# 02_-_MCU.net
KiCad netlist of a schematic drawn in Altium Designer
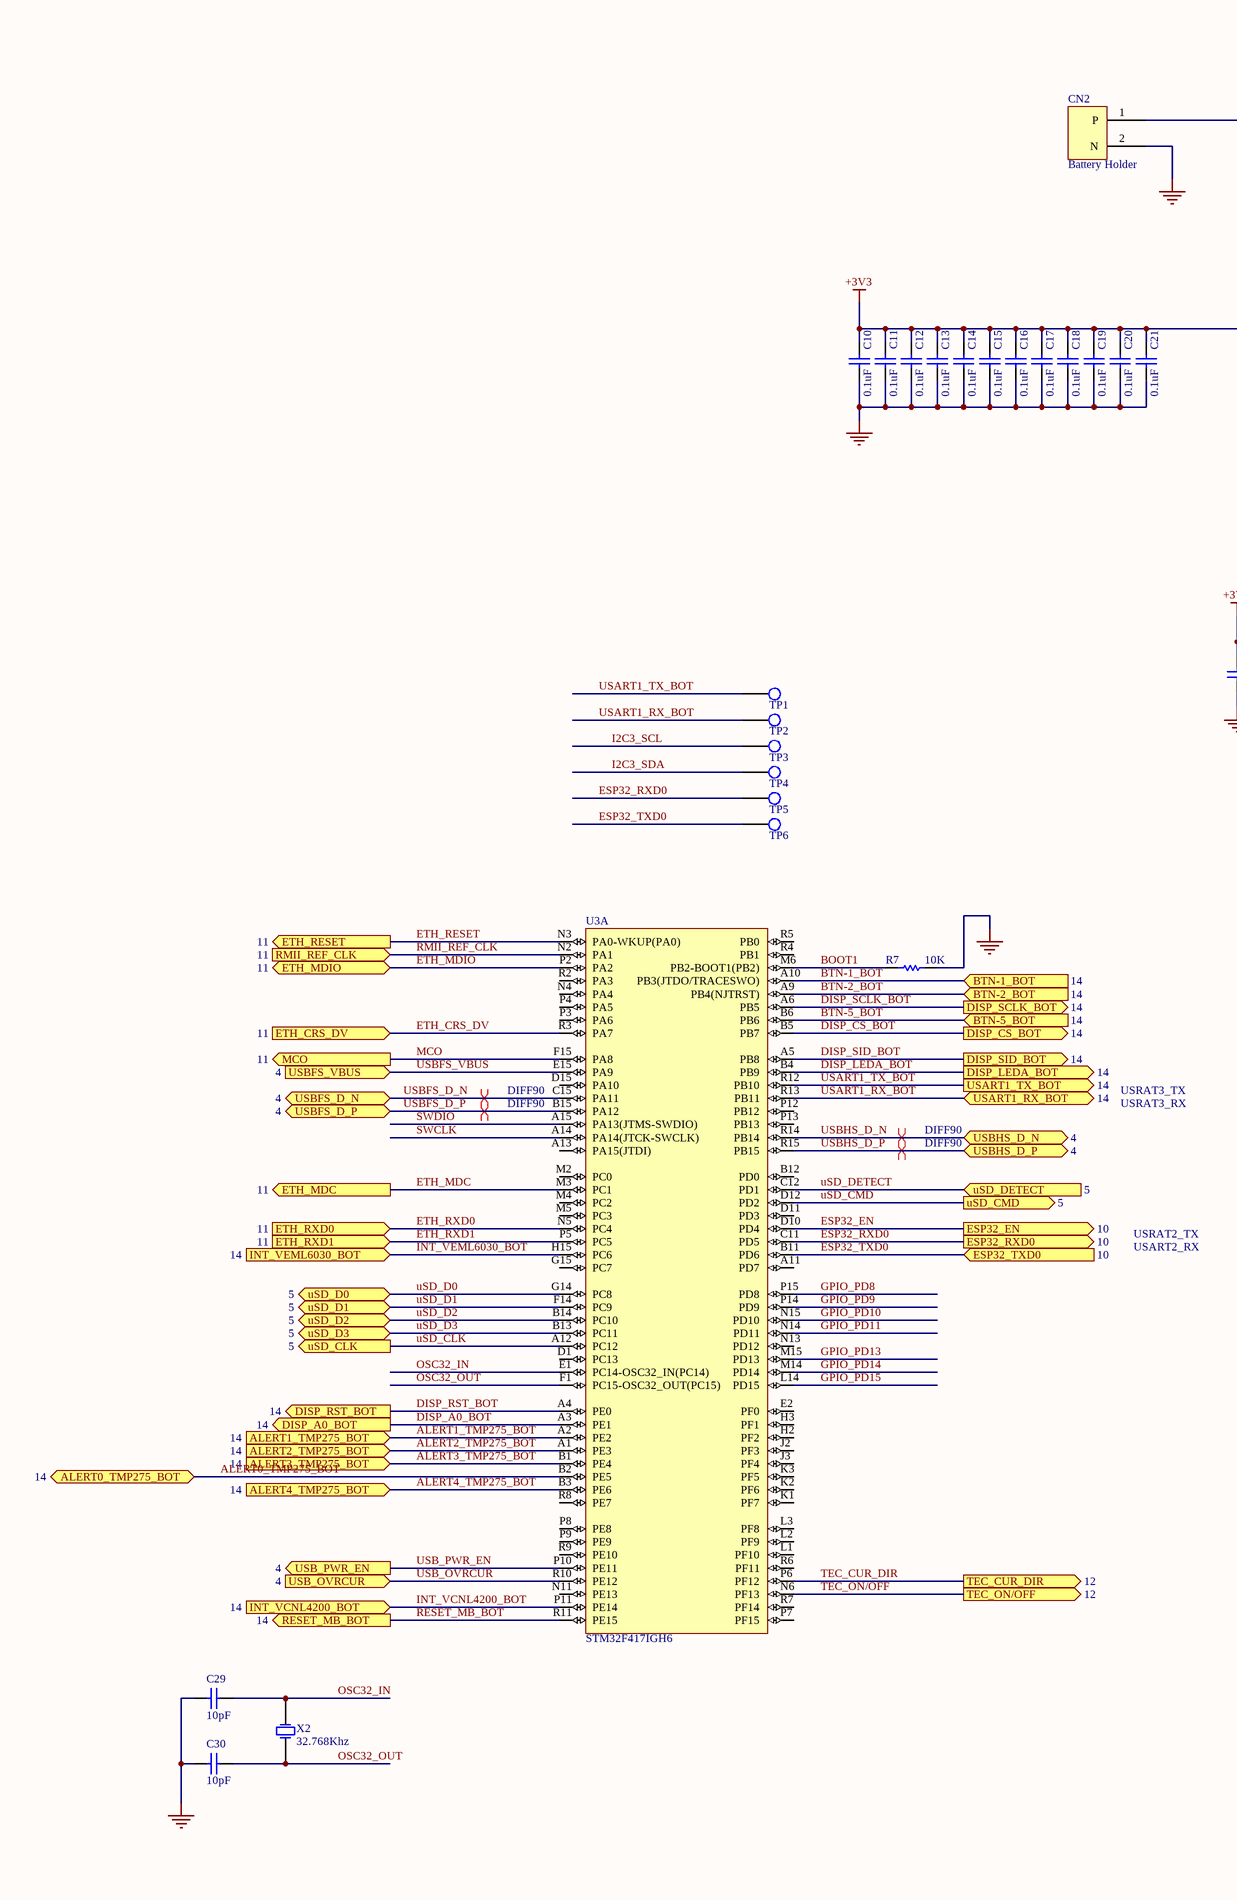
[diagram p0: [02] - MCU.SchDoc, left]
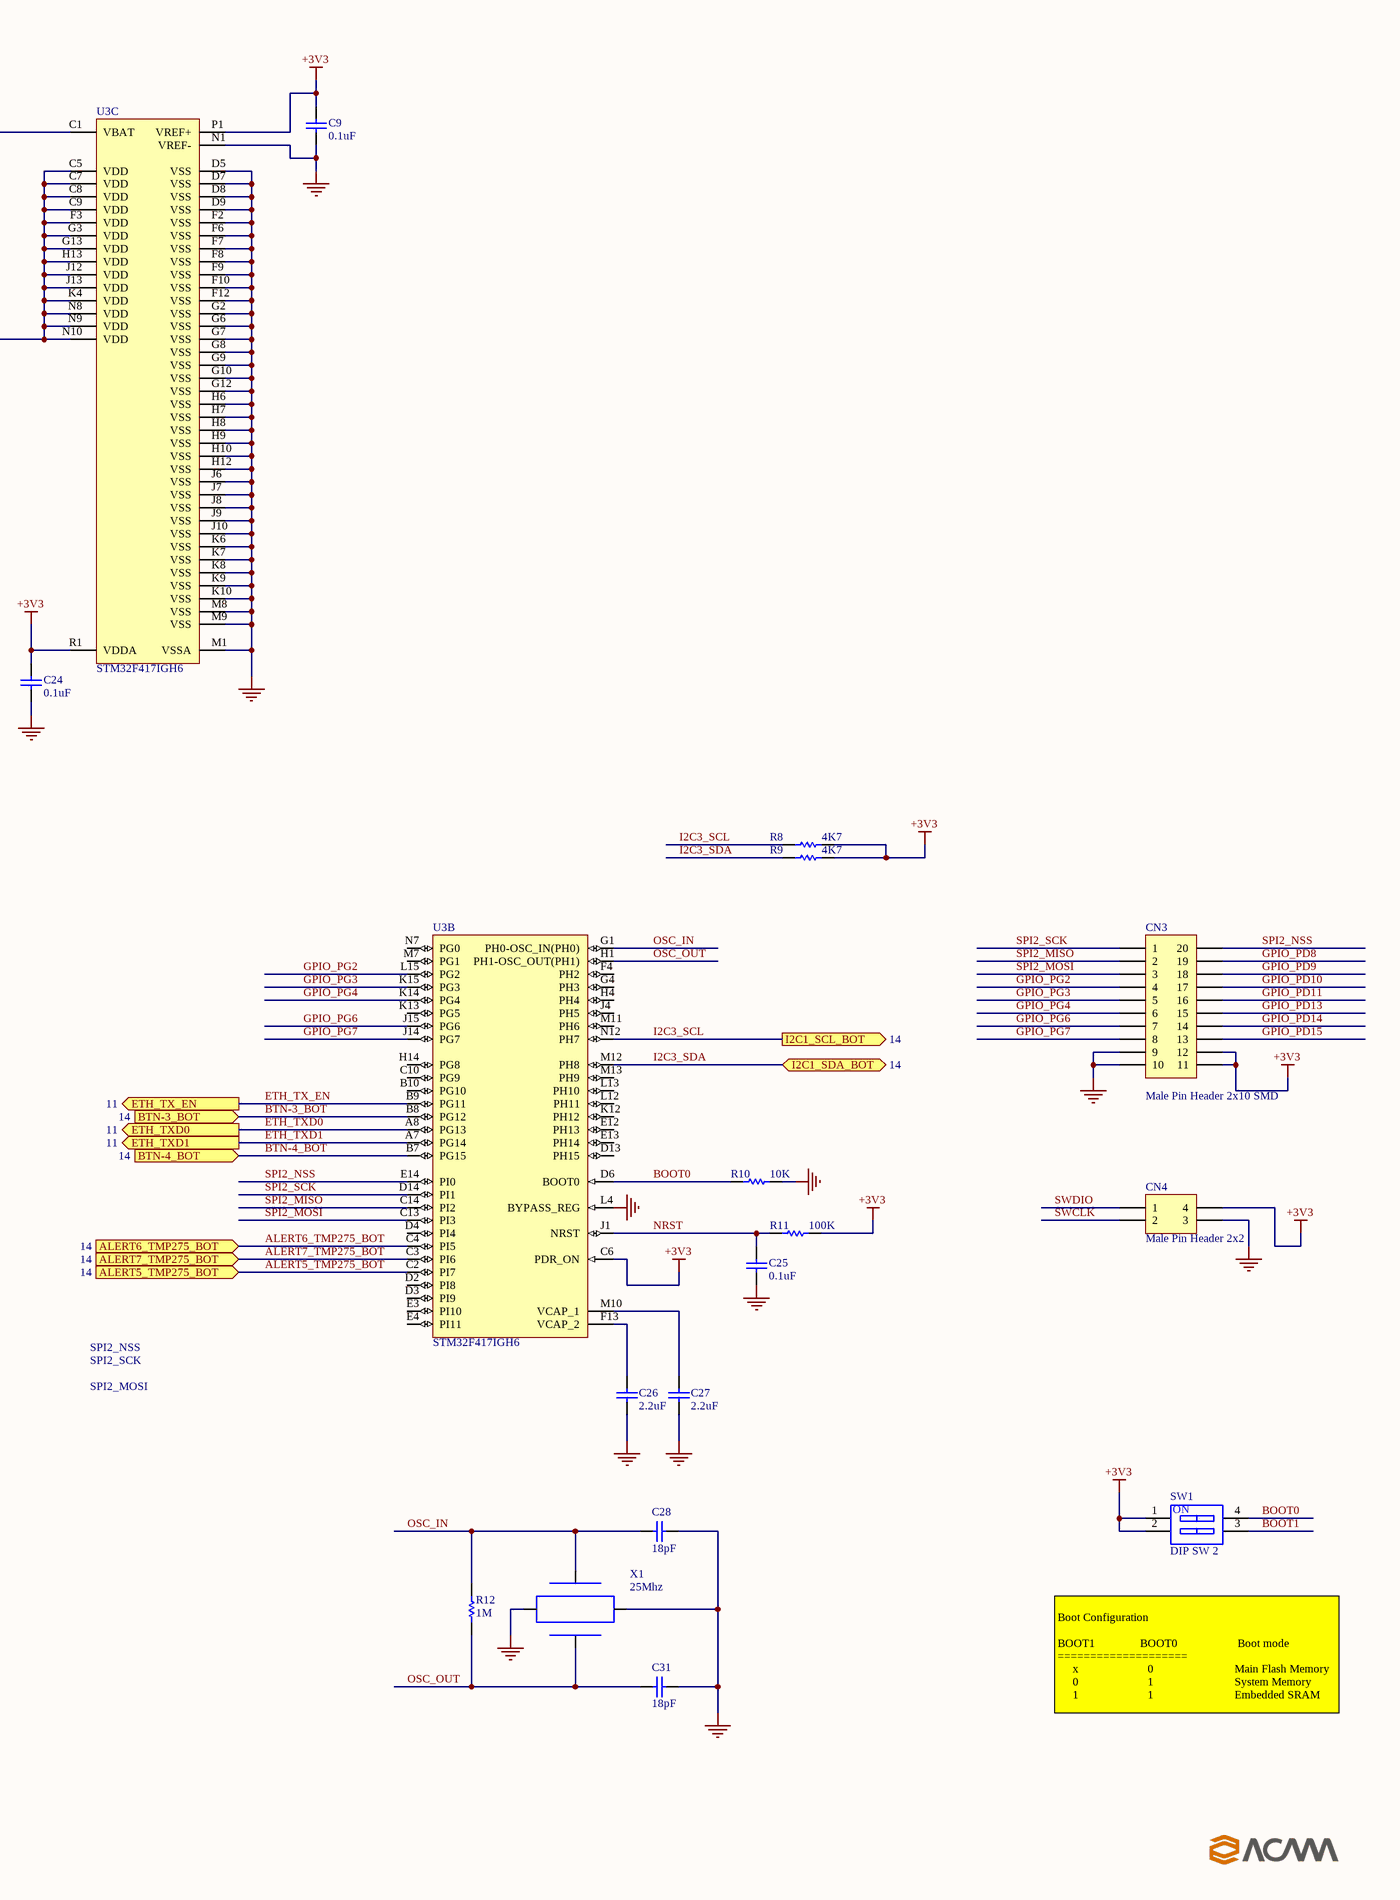
[diagram p1: [02] - MCU.SchDoc, right]

(export (version "E")
  (design (tool "Eeschema 10.0.6"))
  (components
    (comp (ref "C9")
      (value "0.1uF")
      (footprint "0402_C_AUTO")
      (description "Non-Pol SMD Capacitor")
      (libsource (lib "Farzan Custom Library") (part "Cap SMD"))
    )
    (comp (ref "C10")
      (value "0.1uF")
      (footprint "0402_C_AUTO")
      (description "Non-Pol SMD Capacitor")
      (libsource (lib "Farzan Custom Library") (part "Cap SMD"))
    )
    (comp (ref "C11")
      (value "0.1uF")
      (footprint "0402_C_AUTO")
      (description "Non-Pol SMD Capacitor")
      (libsource (lib "Farzan Custom Library") (part "Cap SMD"))
    )
    (comp (ref "C12")
      (value "0.1uF")
      (footprint "0402_C_AUTO")
      (description "Non-Pol SMD Capacitor")
      (libsource (lib "Farzan Custom Library") (part "Cap SMD"))
    )
    (comp (ref "C13")
      (value "0.1uF")
      (footprint "0402_C_AUTO")
      (description "Non-Pol SMD Capacitor")
      (libsource (lib "Farzan Custom Library") (part "Cap SMD"))
    )
    (comp (ref "C14")
      (value "0.1uF")
      (footprint "0402_C_AUTO")
      (description "Non-Pol SMD Capacitor")
      (libsource (lib "Farzan Custom Library") (part "Cap SMD"))
    )
    (comp (ref "C15")
      (value "0.1uF")
      (footprint "0402_C_AUTO")
      (description "Non-Pol SMD Capacitor")
      (libsource (lib "Farzan Custom Library") (part "Cap SMD"))
    )
    (comp (ref "C16")
      (value "0.1uF")
      (footprint "0402_C_AUTO")
      (description "Non-Pol SMD Capacitor")
      (libsource (lib "Farzan Custom Library") (part "Cap SMD"))
    )
    (comp (ref "C17")
      (value "0.1uF")
      (footprint "0402_C_AUTO")
      (description "Non-Pol SMD Capacitor")
      (libsource (lib "Farzan Custom Library") (part "Cap SMD"))
    )
    (comp (ref "C18")
      (value "0.1uF")
      (footprint "0402_C_AUTO")
      (description "Non-Pol SMD Capacitor")
      (libsource (lib "Farzan Custom Library") (part "Cap SMD"))
    )
    (comp (ref "C19")
      (value "0.1uF")
      (footprint "0402_C_AUTO")
      (description "Non-Pol SMD Capacitor")
      (libsource (lib "Farzan Custom Library") (part "Cap SMD"))
    )
    (comp (ref "C20")
      (value "0.1uF")
      (footprint "0402_C_AUTO")
      (description "Non-Pol SMD Capacitor")
      (libsource (lib "Farzan Custom Library") (part "Cap SMD"))
    )
    (comp (ref "C21")
      (value "0.1uF")
      (footprint "0402_C_AUTO")
      (description "Non-Pol SMD Capacitor")
      (libsource (lib "Farzan Custom Library") (part "Cap SMD"))
    )
    (comp (ref "C24")
      (value "0.1uF")
      (footprint "0402_C_AUTO")
      (description "Non-Pol SMD Capacitor")
      (libsource (lib "Farzan Custom Library") (part "Cap SMD"))
    )
    (comp (ref "C25")
      (value "0.1uF")
      (footprint "0402_C_AUTO")
      (description "Non-Pol SMD Capacitor")
      (libsource (lib "Farzan Custom Library") (part "Cap SMD"))
    )
    (comp (ref "C26")
      (value "2.2uF")
      (footprint "0402_C_AUTO")
      (description "Non-Pol SMD Capacitor")
      (libsource (lib "Farzan Custom Library") (part "Cap SMD"))
    )
    (comp (ref "C27")
      (value "2.2uF")
      (footprint "0402_C_AUTO")
      (description "Non-Pol SMD Capacitor")
      (libsource (lib "Farzan Custom Library") (part "Cap SMD"))
    )
    (comp (ref "C28")
      (value "18pF")
      (footprint "0402_C_AUTO")
      (description "Non-Pol SMD Capacitor")
      (libsource (lib "Farzan Custom Library") (part "Cap SMD"))
    )
    (comp (ref "C29")
      (value "10pF")
      (footprint "0402_C_AUTO")
      (description "Non-Pol SMD Capacitor")
      (libsource (lib "Farzan Custom Library") (part "Cap SMD"))
    )
    (comp (ref "C30")
      (value "10pF")
      (footprint "0402_C_AUTO")
      (description "Non-Pol SMD Capacitor")
      (libsource (lib "Farzan Custom Library") (part "Cap SMD"))
    )
    (comp (ref "C31")
      (value "18pF")
      (footprint "0402_C_AUTO")
      (description "Non-Pol SMD Capacitor")
      (libsource (lib "Farzan Custom Library") (part "Cap SMD"))
    )
    (comp (ref "CN2")
      (value "Battery Holder")
      (footprint "CR2032_BATT_HOLDER")
      (description "CR2032 Battery Holder SMD")
      (libsource (lib "Farzan Custom Library") (part "Battery Holder"))
    )
    (comp (ref "CN3")
      (value "Male Pin Header 2x10 SMD")
      (footprint "HEADER_SMD_2x10")
      (description "SMD Male Pin Header 2.54mm Pitch, 2x10")
      (libsource (lib "Farzan Custom Library") (part "Pin header Male 2x10 smd"))
    )
    (comp (ref "CN4")
      (value "Male Pin Header 2x2")
      (footprint "Header_2x2_RIGHT")
      (description "Male Pin Header 2.54mm Pitch, 2x2")
      (libsource (lib "Farzan Custom Library") (part "Pin header Male 2x2"))
    )
    (comp (ref "R7")
      (value "10K")
      (footprint "0402_R_AUTO")
      (description "SMD Resistor")
      (fields (field (name "TOLERANCE") "5%"))
      (libsource (lib "Farzan Custom Library") (part "Res SMD"))
    )
    (comp (ref "R8")
      (value "4K7")
      (footprint "0402_R")
      (description "SMD Resistor")
      (fields (field (name "TOLERANCE") "5%"))
      (libsource (lib "Farzan Custom Library") (part "Res SMD"))
    )
    (comp (ref "R9")
      (value "4K7")
      (footprint "0402_R")
      (description "SMD Resistor")
      (fields (field (name "TOLERANCE") "5%"))
      (libsource (lib "Farzan Custom Library") (part "Res SMD"))
    )
    (comp (ref "R10")
      (value "10K")
      (footprint "0402_R_AUTO")
      (description "SMD Resistor")
      (fields (field (name "TOLERANCE") "5%"))
      (libsource (lib "Farzan Custom Library") (part "Res SMD"))
    )
    (comp (ref "R11")
      (value "100K")
      (footprint "0402_R_AUTO")
      (description "SMD Resistor")
      (fields (field (name "TOLERANCE") "5%"))
      (libsource (lib "Farzan Custom Library") (part "Res SMD"))
    )
    (comp (ref "R12")
      (value "1M")
      (footprint "0402_R")
      (description "SMD Resistor")
      (fields (field (name "TOLERANCE") "5%"))
      (libsource (lib "Farzan Custom Library") (part "Res SMD"))
    )
    (comp (ref "SW1")
      (value "DIP SW 2")
      (footprint "DIP-SW-2-Piano")
      (description "DIP Switch, 2 Position, SPST")
      (fields (field (name "MANUFACTURER PART NUM") "BPA02B"))
      (libsource (lib "Farzan Custom Library") (part "DIP SW-2"))
    )
    (comp (ref "TP1")
      (value "Test Point")
      (footprint "PIN_1.5mm")
      (description "Test Point Footprint")
      (libsource (lib "Farzan Custom Library") (part "Test Point"))
    )
    (comp (ref "TP2")
      (value "Test Point")
      (footprint "PIN_1.5mm")
      (description "Test Point Footprint")
      (libsource (lib "Farzan Custom Library") (part "Test Point"))
    )
    (comp (ref "TP3")
      (value "Test Point")
      (footprint "PIN_1.5mm")
      (description "Test Point Footprint")
      (libsource (lib "Farzan Custom Library") (part "Test Point"))
    )
    (comp (ref "TP4")
      (value "Test Point")
      (footprint "PIN_1.5mm")
      (description "Test Point Footprint")
      (libsource (lib "Farzan Custom Library") (part "Test Point"))
    )
    (comp (ref "TP5")
      (value "Test Point")
      (footprint "PIN_1mm")
      (description "Test Point Footprint")
      (libsource (lib "Farzan Custom Library") (part "Test Point"))
    )
    (comp (ref "TP6")
      (value "Test Point")
      (footprint "PIN_1mm")
      (description "Test Point Footprint")
      (libsource (lib "Farzan Custom Library") (part "Test Point"))
    )
    (comp (ref "U3")
      (value "STM32F417IGH6")
      (footprint "STM-UFBGA176+25")
      (fields (field (name "MANUFACTURER") "STMicroelectronics"))
      (libsource (lib "STMicroelectronics STM32 F4") (part "STM32F417IGH6"))
    )
    (comp (ref "X1")
      (value "25Mhz")
      (footprint "OSC_3.2x2.5")
      (description "4-pin SMD Crystal")
      (fields (field (name "MANUFACTURER PART NUM") "ECS-250-18-33-JTN-TR"))
      (libsource (lib "Farzan Custom Library") (part "XTAL 4pin"))
    )
    (comp (ref "X2")
      (value "32.768Khz")
      (footprint "XTAL_2.0x1.2")
      (description "2-pin SMD Crystal")
      (fields (field (name "MANUFACTURER PART NUM") "ECS-.327-12.5-12R-TR"))
      (libsource (lib "Farzan Custom Library") (part "XTAL"))
    )
  )
  (nets
    (net (code "1") (name "+3V3") (class "Default")
      (node (ref "C10") (pin "2") (pinfunction "2_2") (pintype "passive"))
      (node (ref "C11") (pin "2") (pinfunction "2_2") (pintype "passive"))
      (node (ref "C12") (pin "2") (pinfunction "2_2") (pintype "passive"))
      (node (ref "C13") (pin "2") (pinfunction "2_2") (pintype "passive"))
      (node (ref "C14") (pin "2") (pinfunction "2_2") (pintype "passive"))
      (node (ref "C15") (pin "2") (pinfunction "2_2") (pintype "passive"))
      (node (ref "C16") (pin "2") (pinfunction "2_2") (pintype "passive"))
      (node (ref "C17") (pin "2") (pinfunction "2_2") (pintype "passive"))
      (node (ref "C18") (pin "2") (pinfunction "2_2") (pintype "passive"))
      (node (ref "C19") (pin "2") (pinfunction "2_2") (pintype "passive"))
      (node (ref "C20") (pin "2") (pinfunction "2_2") (pintype "passive"))
      (node (ref "C21") (pin "2") (pinfunction "2_2") (pintype "passive"))
      (node (ref "C24") (pin "2") (pinfunction "2_2") (pintype "passive"))
      (node (ref "C9") (pin "2") (pinfunction "2_2") (pintype "passive"))
      (node (ref "CN3") (pin "11") (pinfunction "11_11") (pintype "passive"))
      (node (ref "CN3") (pin "12") (pinfunction "12_12") (pintype "passive"))
      (node (ref "CN4") (pin "4") (pinfunction "4_4") (pintype "passive"))
      (node (ref "R11") (pin "2") (pinfunction "2_2") (pintype "passive"))
      (node (ref "R8") (pin "1") (pinfunction "1_1") (pintype "passive"))
      (node (ref "R9") (pin "1") (pinfunction "1_1") (pintype "passive"))
      (node (ref "SW1") (pin "1") (pinfunction "A1_1") (pintype "passive"))
      (node (ref "SW1") (pin "2") (pinfunction "A2_2") (pintype "passive"))
      (node (ref "U3") (pin "C5") (pinfunction "VDD_C5") (pintype "power_in"))
      (node (ref "U3") (pin "C6") (pinfunction "PDR_ON_C6") (pintype "input"))
      (node (ref "U3") (pin "C7") (pinfunction "VDD_C7") (pintype "power_in"))
      (node (ref "U3") (pin "C8") (pinfunction "VDD_C8") (pintype "power_in"))
      (node (ref "U3") (pin "C9") (pinfunction "VDD_C9") (pintype "power_in"))
      (node (ref "U3") (pin "F3") (pinfunction "VDD_F3") (pintype "power_in"))
      (node (ref "U3") (pin "G13") (pinfunction "VDD_G13") (pintype "power_in"))
      (node (ref "U3") (pin "G3") (pinfunction "VDD_G3") (pintype "power_in"))
      (node (ref "U3") (pin "H13") (pinfunction "VDD_H13") (pintype "power_in"))
      (node (ref "U3") (pin "J12") (pinfunction "VDD_J12") (pintype "power_in"))
      (node (ref "U3") (pin "J13") (pinfunction "VDD_J13") (pintype "power_in"))
      (node (ref "U3") (pin "K4") (pinfunction "VDD_K4") (pintype "power_in"))
      (node (ref "U3") (pin "N10") (pinfunction "VDD_N10") (pintype "power_in"))
      (node (ref "U3") (pin "N8") (pinfunction "VDD_N8") (pintype "power_in"))
      (node (ref "U3") (pin "N9") (pinfunction "VDD_N9") (pintype "power_in"))
      (node (ref "U3") (pin "P1") (pinfunction "VREF+_P1") (pintype "power_in"))
      (node (ref "U3") (pin "R1") (pinfunction "VDDA_R1") (pintype "power_in"))
    )
    (net (code "2") (name "/ALERT0_TMP275_BOT") (class "Default")
      (node (ref "U3") (pin "B2") (pinfunction "PE5_B2") (pintype "bidirectional"))
    )
    (net (code "3") (name "/ALERT1_TMP275_BOT") (class "Default")
      (node (ref "U3") (pin "A2") (pinfunction "PE2_A2") (pintype "bidirectional"))
    )
    (net (code "4") (name "/ALERT2_TMP275_BOT") (class "Default")
      (node (ref "U3") (pin "A1") (pinfunction "PE3_A1") (pintype "bidirectional"))
    )
    (net (code "5") (name "/ALERT3_TMP275_BOT") (class "Default")
      (node (ref "U3") (pin "B1") (pinfunction "PE4_B1") (pintype "bidirectional"))
    )
    (net (code "6") (name "/ALERT4_TMP275_BOT") (class "Default")
      (node (ref "U3") (pin "B3") (pinfunction "PE6_B3") (pintype "bidirectional"))
    )
    (net (code "7") (name "/ALERT5_TMP275_BOT") (class "Default")
      (node (ref "U3") (pin "C2") (pinfunction "PI7_C2") (pintype "bidirectional"))
    )
    (net (code "8") (name "/ALERT6_TMP275_BOT") (class "Default")
      (node (ref "U3") (pin "C4") (pinfunction "PI5_C4") (pintype "bidirectional"))
    )
    (net (code "9") (name "/ALERT7_TMP275_BOT") (class "Default")
      (node (ref "U3") (pin "C3") (pinfunction "PI6_C3") (pintype "bidirectional"))
    )
    (net (code "10") (name "/BOOT0") (class "Default")
      (node (ref "R10") (pin "1") (pinfunction "1_1") (pintype "passive"))
      (node (ref "SW1") (pin "4") (pinfunction "A4_4") (pintype "passive"))
      (node (ref "U3") (pin "D6") (pinfunction "BOOT0_D6") (pintype "input"))
    )
    (net (code "11") (name "/BOOT1") (class "Default")
      (node (ref "R7") (pin "1") (pinfunction "1_1") (pintype "passive"))
      (node (ref "SW1") (pin "3") (pinfunction "A3_3") (pintype "passive"))
      (node (ref "U3") (pin "M6") (pinfunction "PB2-BOOT1(PB2)_M6") (pintype "bidirectional"))
    )
    (net (code "12") (name "/BTN-1_BOT") (class "Default")
      (node (ref "U3") (pin "A10") (pinfunction "PB3(JTDO/TRACESWO)_A10") (pintype "bidirectional"))
    )
    (net (code "13") (name "/BTN-2_BOT") (class "Default")
      (node (ref "U3") (pin "A9") (pinfunction "PB4(NJTRST)_A9") (pintype "bidirectional"))
    )
    (net (code "14") (name "/BTN-3_BOT") (class "Default")
      (node (ref "U3") (pin "B8") (pinfunction "PG12_B8") (pintype "bidirectional"))
    )
    (net (code "15") (name "/BTN-4_BOT") (class "Default")
      (node (ref "U3") (pin "B7") (pinfunction "PG15_B7") (pintype "bidirectional"))
    )
    (net (code "16") (name "/BTN-5_BOT") (class "Default")
      (node (ref "U3") (pin "B6") (pinfunction "PB6_B6") (pintype "bidirectional"))
    )
    (net (code "17") (name "/DISP_A0_BOT") (class "Default")
      (node (ref "U3") (pin "A3") (pinfunction "PE1_A3") (pintype "bidirectional"))
    )
    (net (code "18") (name "/DISP_CS_BOT") (class "Default")
      (node (ref "U3") (pin "B5") (pinfunction "PB7_B5") (pintype "bidirectional"))
    )
    (net (code "19") (name "/DISP_LEDA_BOT") (class "Default")
      (node (ref "U3") (pin "B4") (pinfunction "PB9_B4") (pintype "bidirectional"))
    )
    (net (code "20") (name "/DISP_RST_BOT") (class "Default")
      (node (ref "U3") (pin "A4") (pinfunction "PE0_A4") (pintype "bidirectional"))
    )
    (net (code "21") (name "/DISP_SCLK_BOT") (class "Default")
      (node (ref "U3") (pin "A6") (pinfunction "PB5_A6") (pintype "bidirectional"))
    )
    (net (code "22") (name "/DISP_SID_BOT") (class "Default")
      (node (ref "U3") (pin "A5") (pinfunction "PB8_A5") (pintype "bidirectional"))
    )
    (net (code "23") (name "/ESP32_EN") (class "Default")
      (node (ref "U3") (pin "D10") (pinfunction "PD4_D10") (pintype "bidirectional"))
    )
    (net (code "24") (name "/ESP32_RXD0") (class "Default")
      (node (ref "TP5") (pin "1") (pinfunction "1_1") (pintype "power_in"))
      (node (ref "U3") (pin "C11") (pinfunction "PD5_C11") (pintype "bidirectional"))
    )
    (net (code "25") (name "/ESP32_TXD0") (class "Default")
      (node (ref "TP6") (pin "1") (pinfunction "1_1") (pintype "power_in"))
      (node (ref "U3") (pin "B11") (pinfunction "PD6_B11") (pintype "bidirectional"))
    )
    (net (code "26") (name "/ETH_CRS_DV") (class "Default")
      (node (ref "U3") (pin "R3") (pinfunction "PA7_R3") (pintype "bidirectional"))
    )
    (net (code "27") (name "/ETH_MDC") (class "Default")
      (node (ref "U3") (pin "M3") (pinfunction "PC1_M3") (pintype "bidirectional"))
    )
    (net (code "28") (name "/ETH_MDIO") (class "Default")
      (node (ref "U3") (pin "P2") (pinfunction "PA2_P2") (pintype "bidirectional"))
    )
    (net (code "29") (name "/ETH_RESET") (class "Default")
      (node (ref "U3") (pin "N3") (pinfunction "PA0-WKUP(PA0)_N3") (pintype "bidirectional"))
    )
    (net (code "30") (name "/ETH_RXD0") (class "Default")
      (node (ref "U3") (pin "N5") (pinfunction "PC4_N5") (pintype "bidirectional"))
    )
    (net (code "31") (name "/ETH_RXD1") (class "Default")
      (node (ref "U3") (pin "P5") (pinfunction "PC5_P5") (pintype "bidirectional"))
    )
    (net (code "32") (name "/ETH_TXD0") (class "Default")
      (node (ref "U3") (pin "A8") (pinfunction "PG13_A8") (pintype "bidirectional"))
    )
    (net (code "33") (name "/ETH_TXD1") (class "Default")
      (node (ref "U3") (pin "A7") (pinfunction "PG14_A7") (pintype "bidirectional"))
    )
    (net (code "34") (name "/ETH_TX_EN") (class "Default")
      (node (ref "U3") (pin "B9") (pinfunction "PG11_B9") (pintype "bidirectional"))
    )
    (net (code "35") (name "/GPIO_PD8") (class "Default")
      (node (ref "CN3") (pin "19") (pinfunction "19_19") (pintype "passive"))
      (node (ref "U3") (pin "P15") (pinfunction "PD8_P15") (pintype "bidirectional"))
    )
    (net (code "36") (name "/GPIO_PD9") (class "Default")
      (node (ref "CN3") (pin "18") (pinfunction "18_18") (pintype "passive"))
      (node (ref "U3") (pin "P14") (pinfunction "PD9_P14") (pintype "bidirectional"))
    )
    (net (code "37") (name "/GPIO_PD10") (class "Default")
      (node (ref "CN3") (pin "17") (pinfunction "17_17") (pintype "passive"))
      (node (ref "U3") (pin "N15") (pinfunction "PD10_N15") (pintype "bidirectional"))
    )
    (net (code "38") (name "/GPIO_PD11") (class "Default")
      (node (ref "CN3") (pin "16") (pinfunction "16_16") (pintype "passive"))
      (node (ref "U3") (pin "N14") (pinfunction "PD11_N14") (pintype "bidirectional"))
    )
    (net (code "39") (name "/GPIO_PD13") (class "Default")
      (node (ref "CN3") (pin "15") (pinfunction "15_15") (pintype "passive"))
      (node (ref "U3") (pin "M15") (pinfunction "PD13_M15") (pintype "bidirectional"))
    )
    (net (code "40") (name "/GPIO_PD14") (class "Default")
      (node (ref "CN3") (pin "14") (pinfunction "14_14") (pintype "passive"))
      (node (ref "U3") (pin "M14") (pinfunction "PD14_M14") (pintype "bidirectional"))
    )
    (net (code "41") (name "/GPIO_PD15") (class "Default")
      (node (ref "CN3") (pin "13") (pinfunction "13_13") (pintype "passive"))
      (node (ref "U3") (pin "L14") (pinfunction "PD15_L14") (pintype "bidirectional"))
    )
    (net (code "42") (name "/GPIO_PG2") (class "Default")
      (node (ref "CN3") (pin "4") (pinfunction "4_4") (pintype "passive"))
      (node (ref "U3") (pin "L15") (pinfunction "PG2_L15") (pintype "bidirectional"))
    )
    (net (code "43") (name "/GPIO_PG3") (class "Default")
      (node (ref "CN3") (pin "5") (pinfunction "5_5") (pintype "passive"))
      (node (ref "U3") (pin "K15") (pinfunction "PG3_K15") (pintype "bidirectional"))
    )
    (net (code "44") (name "/GPIO_PG4") (class "Default")
      (node (ref "CN3") (pin "6") (pinfunction "6_6") (pintype "passive"))
      (node (ref "U3") (pin "K14") (pinfunction "PG4_K14") (pintype "bidirectional"))
    )
    (net (code "45") (name "/GPIO_PG6") (class "Default")
      (node (ref "CN3") (pin "7") (pinfunction "7_7") (pintype "passive"))
      (node (ref "U3") (pin "J15") (pinfunction "PG6_J15") (pintype "bidirectional"))
    )
    (net (code "46") (name "/GPIO_PG7") (class "Default")
      (node (ref "CN3") (pin "8") (pinfunction "8_8") (pintype "passive"))
      (node (ref "U3") (pin "J14") (pinfunction "PG7_J14") (pintype "bidirectional"))
    )
    (net (code "47") (name "/I2C3_SCL") (class "Default")
      (node (ref "R8") (pin "2") (pinfunction "2_2") (pintype "passive"))
      (node (ref "TP3") (pin "1") (pinfunction "1_1") (pintype "power_in"))
      (node (ref "U3") (pin "N12") (pinfunction "PH7_N12") (pintype "bidirectional"))
    )
    (net (code "48") (name "/I2C3_SDA") (class "Default")
      (node (ref "R9") (pin "2") (pinfunction "2_2") (pintype "passive"))
      (node (ref "TP4") (pin "1") (pinfunction "1_1") (pintype "power_in"))
      (node (ref "U3") (pin "M12") (pinfunction "PH8_M12") (pintype "bidirectional"))
    )
    (net (code "49") (name "/INT_VCNL4200_BOT") (class "Default")
      (node (ref "U3") (pin "P11") (pinfunction "PE14_P11") (pintype "bidirectional"))
    )
    (net (code "50") (name "/INT_VEML6030_BOT") (class "Default")
      (node (ref "U3") (pin "H15") (pinfunction "PC6_H15") (pintype "bidirectional"))
    )
    (net (code "51") (name "/MCO") (class "Default")
      (node (ref "U3") (pin "F15") (pinfunction "PA8_F15") (pintype "bidirectional"))
    )
    (net (code "52") (name "/NRST") (class "Default")
      (node (ref "C25") (pin "2") (pinfunction "2_2") (pintype "passive"))
      (node (ref "R11") (pin "1") (pinfunction "1_1") (pintype "passive"))
      (node (ref "U3") (pin "J1") (pinfunction "NRST_J1") (pintype "bidirectional"))
    )
    (net (code "53") (name "/OSC32_IN") (class "Default")
      (node (ref "C29") (pin "2") (pinfunction "2_2") (pintype "passive"))
      (node (ref "U3") (pin "E1") (pinfunction "PC14-OSC32_IN(PC14)_E1") (pintype "bidirectional"))
      (node (ref "X2") (pin "1") (pinfunction "OSC1_1") (pintype "passive"))
    )
    (net (code "54") (name "/OSC32_OUT") (class "Default")
      (node (ref "C30") (pin "2") (pinfunction "2_2") (pintype "passive"))
      (node (ref "U3") (pin "F1") (pinfunction "PC15-OSC32_OUT(PC15)_F1") (pintype "bidirectional"))
      (node (ref "X2") (pin "2") (pinfunction "OSC2_2") (pintype "passive"))
    )
    (net (code "55") (name "/OSC_IN") (class "Default")
      (node (ref "C28") (pin "1") (pinfunction "1_1") (pintype "passive"))
      (node (ref "R12") (pin "2") (pinfunction "2_2") (pintype "passive"))
      (node (ref "U3") (pin "G1") (pinfunction "PH0-OSC_IN(PH0)_G1") (pintype "bidirectional"))
      (node (ref "X1") (pin "1") (pinfunction "1_1") (pintype "passive"))
    )
    (net (code "56") (name "/OSC_OUT") (class "Default")
      (node (ref "C31") (pin "1") (pinfunction "1_1") (pintype "passive"))
      (node (ref "R12") (pin "1") (pinfunction "1_1") (pintype "passive"))
      (node (ref "U3") (pin "H1") (pinfunction "PH1-OSC_OUT(PH1)_H1") (pintype "bidirectional"))
      (node (ref "X1") (pin "3") (pinfunction "3_3") (pintype "passive"))
    )
    (net (code "57") (name "/RESET_MB_BOT") (class "Default")
      (node (ref "U3") (pin "R11") (pinfunction "PE15_R11") (pintype "bidirectional"))
    )
    (net (code "58") (name "/RMII_REF_CLK") (class "Default")
      (node (ref "U3") (pin "N2") (pinfunction "PA1_N2") (pintype "bidirectional"))
    )
    (net (code "59") (name "/SPI2_MISO") (class "Default")
      (node (ref "CN3") (pin "2") (pinfunction "2_2") (pintype "passive"))
      (node (ref "U3") (pin "C14") (pinfunction "PI2_C14") (pintype "bidirectional"))
    )
    (net (code "60") (name "/SPI2_MOSI") (class "Default")
      (node (ref "CN3") (pin "3") (pinfunction "3_3") (pintype "passive"))
      (node (ref "U3") (pin "C13") (pinfunction "PI3_C13") (pintype "bidirectional"))
    )
    (net (code "61") (name "/SPI2_NSS") (class "Default")
      (node (ref "CN3") (pin "20") (pinfunction "20_20") (pintype "passive"))
      (node (ref "U3") (pin "E14") (pinfunction "PI0_E14") (pintype "bidirectional"))
    )
    (net (code "62") (name "/SPI2_SCK") (class "Default")
      (node (ref "CN3") (pin "1") (pinfunction "1_1") (pintype "passive"))
      (node (ref "U3") (pin "D14") (pinfunction "PI1_D14") (pintype "bidirectional"))
    )
    (net (code "63") (name "/SWCLK") (class "Default")
      (node (ref "CN4") (pin "2") (pinfunction "2_2") (pintype "passive"))
      (node (ref "U3") (pin "A14") (pinfunction "PA14(JTCK-SWCLK)_A14") (pintype "bidirectional"))
    )
    (net (code "64") (name "/SWDIO") (class "Default")
      (node (ref "CN4") (pin "1") (pinfunction "1_1") (pintype "passive"))
      (node (ref "U3") (pin "A15") (pinfunction "PA13(JTMS-SWDIO)_A15") (pintype "bidirectional"))
    )
    (net (code "65") (name "/TEC_CUR_DIR") (class "Default")
      (node (ref "U3") (pin "P6") (pinfunction "PF12_P6") (pintype "bidirectional"))
    )
    (net (code "66") (name "/TEC_ON{slash}OFF") (class "Default")
      (node (ref "U3") (pin "N6") (pinfunction "PF13_N6") (pintype "bidirectional"))
    )
    (net (code "67") (name "/USART1_RX_BOT") (class "Default")
      (node (ref "TP2") (pin "1") (pinfunction "1_1") (pintype "power_in"))
      (node (ref "U3") (pin "R13") (pinfunction "PB11_R13") (pintype "bidirectional"))
    )
    (net (code "68") (name "/USART1_TX_BOT") (class "Default")
      (node (ref "TP1") (pin "1") (pinfunction "1_1") (pintype "power_in"))
      (node (ref "U3") (pin "R12") (pinfunction "PB10_R12") (pintype "bidirectional"))
    )
    (net (code "69") (name "/USBFS_D_N") (class "Default")
      (node (ref "U3") (pin "C15") (pinfunction "PA11_C15") (pintype "bidirectional"))
    )
    (net (code "70") (name "/USBFS_D_P") (class "Default")
      (node (ref "U3") (pin "B15") (pinfunction "PA12_B15") (pintype "bidirectional"))
    )
    (net (code "71") (name "/USBFS_VBUS") (class "Default")
      (node (ref "U3") (pin "E15") (pinfunction "PA9_E15") (pintype "bidirectional"))
    )
    (net (code "72") (name "/USBHS_D_N") (class "Default")
      (node (ref "U3") (pin "R14") (pinfunction "PB14_R14") (pintype "bidirectional"))
    )
    (net (code "73") (name "/USBHS_D_P") (class "Default")
      (node (ref "U3") (pin "R15") (pinfunction "PB15_R15") (pintype "bidirectional"))
    )
    (net (code "74") (name "/USB_OVRCUR") (class "Default")
      (node (ref "U3") (pin "R10") (pinfunction "PE12_R10") (pintype "bidirectional"))
    )
    (net (code "75") (name "/USB_PWR_EN") (class "Default")
      (node (ref "U3") (pin "P10") (pinfunction "PE11_P10") (pintype "bidirectional"))
    )
    (net (code "76") (name "/uSD_CLK") (class "Default")
      (node (ref "U3") (pin "A12") (pinfunction "PC12_A12") (pintype "bidirectional"))
    )
    (net (code "77") (name "/uSD_CMD") (class "Default")
      (node (ref "U3") (pin "D12") (pinfunction "PD2_D12") (pintype "bidirectional"))
    )
    (net (code "78") (name "/uSD_D0") (class "Default")
      (node (ref "U3") (pin "G14") (pinfunction "PC8_G14") (pintype "bidirectional"))
    )
    (net (code "79") (name "/uSD_D1") (class "Default")
      (node (ref "U3") (pin "F14") (pinfunction "PC9_F14") (pintype "bidirectional"))
    )
    (net (code "80") (name "/uSD_D2") (class "Default")
      (node (ref "U3") (pin "B14") (pinfunction "PC10_B14") (pintype "bidirectional"))
    )
    (net (code "81") (name "/uSD_D3") (class "Default")
      (node (ref "U3") (pin "B13") (pinfunction "PC11_B13") (pintype "bidirectional"))
    )
    (net (code "82") (name "/uSD_DETECT") (class "Default")
      (node (ref "U3") (pin "C12") (pinfunction "PD1_C12") (pintype "bidirectional"))
    )
    (net (code "83") (name "GND") (class "Default")
      (node (ref "C10") (pin "1") (pinfunction "1_1") (pintype "passive"))
      (node (ref "C11") (pin "1") (pinfunction "1_1") (pintype "passive"))
      (node (ref "C12") (pin "1") (pinfunction "1_1") (pintype "passive"))
      (node (ref "C13") (pin "1") (pinfunction "1_1") (pintype "passive"))
      (node (ref "C14") (pin "1") (pinfunction "1_1") (pintype "passive"))
      (node (ref "C15") (pin "1") (pinfunction "1_1") (pintype "passive"))
      (node (ref "C16") (pin "1") (pinfunction "1_1") (pintype "passive"))
      (node (ref "C17") (pin "1") (pinfunction "1_1") (pintype "passive"))
      (node (ref "C18") (pin "1") (pinfunction "1_1") (pintype "passive"))
      (node (ref "C19") (pin "1") (pinfunction "1_1") (pintype "passive"))
      (node (ref "C20") (pin "1") (pinfunction "1_1") (pintype "passive"))
      (node (ref "C21") (pin "1") (pinfunction "1_1") (pintype "passive"))
      (node (ref "C24") (pin "1") (pinfunction "1_1") (pintype "passive"))
      (node (ref "C25") (pin "1") (pinfunction "1_1") (pintype "passive"))
      (node (ref "C26") (pin "1") (pinfunction "1_1") (pintype "passive"))
      (node (ref "C27") (pin "1") (pinfunction "1_1") (pintype "passive"))
      (node (ref "C28") (pin "2") (pinfunction "2_2") (pintype "passive"))
      (node (ref "C29") (pin "1") (pinfunction "1_1") (pintype "passive"))
      (node (ref "C30") (pin "1") (pinfunction "1_1") (pintype "passive"))
      (node (ref "C31") (pin "2") (pinfunction "2_2") (pintype "passive"))
      (node (ref "C9") (pin "1") (pinfunction "1_1") (pintype "passive"))
      (node (ref "CN2") (pin "2") (pinfunction "N_2") (pintype "passive"))
      (node (ref "CN3") (pin "10") (pinfunction "10_10") (pintype "passive"))
      (node (ref "CN3") (pin "9") (pinfunction "9_9") (pintype "passive"))
      (node (ref "CN4") (pin "3") (pinfunction "3_3") (pintype "passive"))
      (node (ref "R10") (pin "2") (pinfunction "2_2") (pintype "passive"))
      (node (ref "R7") (pin "2") (pinfunction "2_2") (pintype "passive"))
      (node (ref "U3") (pin "D5") (pinfunction "VSS_D5") (pintype "power_in"))
      (node (ref "U3") (pin "D7") (pinfunction "VSS_D7") (pintype "power_in"))
      (node (ref "U3") (pin "D8") (pinfunction "VSS_D8") (pintype "power_in"))
      (node (ref "U3") (pin "D9") (pinfunction "VSS_D9") (pintype "power_in"))
      (node (ref "U3") (pin "F10") (pinfunction "VSS_F10") (pintype "power_in"))
      (node (ref "U3") (pin "F12") (pinfunction "VSS_F12") (pintype "power_in"))
      (node (ref "U3") (pin "F2") (pinfunction "VSS_F2") (pintype "power_in"))
      (node (ref "U3") (pin "F6") (pinfunction "VSS_F6") (pintype "power_in"))
      (node (ref "U3") (pin "F7") (pinfunction "VSS_F7") (pintype "power_in"))
      (node (ref "U3") (pin "F8") (pinfunction "VSS_F8") (pintype "power_in"))
      (node (ref "U3") (pin "F9") (pinfunction "VSS_F9") (pintype "power_in"))
      (node (ref "U3") (pin "G10") (pinfunction "VSS_G10") (pintype "power_in"))
      (node (ref "U3") (pin "G12") (pinfunction "VSS_G12") (pintype "power_in"))
      (node (ref "U3") (pin "G2") (pinfunction "VSS_G2") (pintype "power_in"))
      (node (ref "U3") (pin "G6") (pinfunction "VSS_G6") (pintype "power_in"))
      (node (ref "U3") (pin "G7") (pinfunction "VSS_G7") (pintype "power_in"))
      (node (ref "U3") (pin "G8") (pinfunction "VSS_G8") (pintype "power_in"))
      (node (ref "U3") (pin "G9") (pinfunction "VSS_G9") (pintype "power_in"))
      (node (ref "U3") (pin "H10") (pinfunction "VSS_H10") (pintype "power_in"))
      (node (ref "U3") (pin "H12") (pinfunction "VSS_H12") (pintype "power_in"))
      (node (ref "U3") (pin "H6") (pinfunction "VSS_H6") (pintype "power_in"))
      (node (ref "U3") (pin "H7") (pinfunction "VSS_H7") (pintype "power_in"))
      (node (ref "U3") (pin "H8") (pinfunction "VSS_H8") (pintype "power_in"))
      (node (ref "U3") (pin "H9") (pinfunction "VSS_H9") (pintype "power_in"))
      (node (ref "U3") (pin "J10") (pinfunction "VSS_J10") (pintype "power_in"))
      (node (ref "U3") (pin "J6") (pinfunction "VSS_J6") (pintype "power_in"))
      (node (ref "U3") (pin "J7") (pinfunction "VSS_J7") (pintype "power_in"))
      (node (ref "U3") (pin "J8") (pinfunction "VSS_J8") (pintype "power_in"))
      (node (ref "U3") (pin "J9") (pinfunction "VSS_J9") (pintype "power_in"))
      (node (ref "U3") (pin "K10") (pinfunction "VSS_K10") (pintype "power_in"))
      (node (ref "U3") (pin "K6") (pinfunction "VSS_K6") (pintype "power_in"))
      (node (ref "U3") (pin "K7") (pinfunction "VSS_K7") (pintype "power_in"))
      (node (ref "U3") (pin "K8") (pinfunction "VSS_K8") (pintype "power_in"))
      (node (ref "U3") (pin "K9") (pinfunction "VSS_K9") (pintype "power_in"))
      (node (ref "U3") (pin "L4") (pinfunction "BYPASS_REG_L4") (pintype "input"))
      (node (ref "U3") (pin "M1") (pinfunction "VSSA_M1") (pintype "power_in"))
      (node (ref "U3") (pin "M8") (pinfunction "VSS_M8") (pintype "power_in"))
      (node (ref "U3") (pin "M9") (pinfunction "VSS_M9") (pintype "power_in"))
      (node (ref "U3") (pin "N1") (pinfunction "VREF-_N1") (pintype "power_in"))
      (node (ref "X1") (pin "2") (pinfunction "GND1_2") (pintype "passive"))
      (node (ref "X1") (pin "4") (pinfunction "GND2_4") (pintype "passive"))
    )
    (net (code "84") (name "Net-(CN2-P)") (class "Default")
      (node (ref "CN2") (pin "1") (pinfunction "P_1") (pintype "passive"))
      (node (ref "U3") (pin "C1") (pinfunction "VBAT_C1") (pintype "power_in"))
    )
    (net (code "85") (name "Net-(U3B-VCAP_1)") (class "Default")
      (node (ref "C27") (pin "2") (pinfunction "2_2") (pintype "passive"))
      (node (ref "U3") (pin "M10") (pinfunction "VCAP_1_M10") (pintype "power_in"))
    )
    (net (code "86") (name "Net-(U3B-VCAP_2)") (class "Default")
      (node (ref "C26") (pin "2") (pinfunction "2_2") (pintype "passive"))
      (node (ref "U3") (pin "F13") (pinfunction "VCAP_2_F13") (pintype "power_in"))
    )
    (net (code "87") (name "unconnected-(U3A-PA3-PadR2)") (class "Default")
      (node (ref "U3") (pin "R2") (pinfunction "PA3_R2") (pintype "bidirectional"))
    )
    (net (code "88") (name "unconnected-(U3A-PA4-PadN4)") (class "Default")
      (node (ref "U3") (pin "N4") (pinfunction "PA4_N4") (pintype "bidirectional"))
    )
    (net (code "89") (name "unconnected-(U3A-PA5-PadP4)") (class "Default")
      (node (ref "U3") (pin "P4") (pinfunction "PA5_P4") (pintype "bidirectional"))
    )
    (net (code "90") (name "unconnected-(U3A-PA6-PadP3)") (class "Default")
      (node (ref "U3") (pin "P3") (pinfunction "PA6_P3") (pintype "bidirectional"))
    )
    (net (code "91") (name "unconnected-(U3A-PA10-PadD15)") (class "Default")
      (node (ref "U3") (pin "D15") (pinfunction "PA10_D15") (pintype "bidirectional"))
    )
    (net (code "92") (name "unconnected-(U3A-PA15(JTDI)-PadA13)") (class "Default")
      (node (ref "U3") (pin "A13") (pinfunction "PA15(JTDI)_A13") (pintype "bidirectional"))
    )
    (net (code "93") (name "unconnected-(U3A-PB0-PadR5)") (class "Default")
      (node (ref "U3") (pin "R5") (pinfunction "PB0_R5") (pintype "bidirectional"))
    )
    (net (code "94") (name "unconnected-(U3A-PB1-PadR4)") (class "Default")
      (node (ref "U3") (pin "R4") (pinfunction "PB1_R4") (pintype "bidirectional"))
    )
    (net (code "95") (name "unconnected-(U3A-PB12-PadP12)") (class "Default")
      (node (ref "U3") (pin "P12") (pinfunction "PB12_P12") (pintype "bidirectional"))
    )
    (net (code "96") (name "unconnected-(U3A-PB13-PadP13)") (class "Default")
      (node (ref "U3") (pin "P13") (pinfunction "PB13_P13") (pintype "bidirectional"))
    )
    (net (code "97") (name "unconnected-(U3A-PC0-PadM2)") (class "Default")
      (node (ref "U3") (pin "M2") (pinfunction "PC0_M2") (pintype "bidirectional"))
    )
    (net (code "98") (name "unconnected-(U3A-PC2-PadM4)") (class "Default")
      (node (ref "U3") (pin "M4") (pinfunction "PC2_M4") (pintype "bidirectional"))
    )
    (net (code "99") (name "unconnected-(U3A-PC3-PadM5)") (class "Default")
      (node (ref "U3") (pin "M5") (pinfunction "PC3_M5") (pintype "bidirectional"))
    )
    (net (code "100") (name "unconnected-(U3A-PC7-PadG15)") (class "Default")
      (node (ref "U3") (pin "G15") (pinfunction "PC7_G15") (pintype "bidirectional"))
    )
    (net (code "101") (name "unconnected-(U3A-PC13-PadD1)") (class "Default")
      (node (ref "U3") (pin "D1") (pinfunction "PC13_D1") (pintype "bidirectional"))
    )
    (net (code "102") (name "unconnected-(U3A-PD0-PadB12)") (class "Default")
      (node (ref "U3") (pin "B12") (pinfunction "PD0_B12") (pintype "bidirectional"))
    )
    (net (code "103") (name "unconnected-(U3A-PD3-PadD11)") (class "Default")
      (node (ref "U3") (pin "D11") (pinfunction "PD3_D11") (pintype "bidirectional"))
    )
    (net (code "104") (name "unconnected-(U3A-PD7-PadA11)") (class "Default")
      (node (ref "U3") (pin "A11") (pinfunction "PD7_A11") (pintype "bidirectional"))
    )
    (net (code "105") (name "unconnected-(U3A-PD12-PadN13)") (class "Default")
      (node (ref "U3") (pin "N13") (pinfunction "PD12_N13") (pintype "bidirectional"))
    )
    (net (code "106") (name "unconnected-(U3A-PE7-PadR8)") (class "Default")
      (node (ref "U3") (pin "R8") (pinfunction "PE7_R8") (pintype "bidirectional"))
    )
    (net (code "107") (name "unconnected-(U3A-PE8-PadP8)") (class "Default")
      (node (ref "U3") (pin "P8") (pinfunction "PE8_P8") (pintype "bidirectional"))
    )
    (net (code "108") (name "unconnected-(U3A-PE9-PadP9)") (class "Default")
      (node (ref "U3") (pin "P9") (pinfunction "PE9_P9") (pintype "bidirectional"))
    )
    (net (code "109") (name "unconnected-(U3A-PE10-PadR9)") (class "Default")
      (node (ref "U3") (pin "R9") (pinfunction "PE10_R9") (pintype "bidirectional"))
    )
    (net (code "110") (name "unconnected-(U3A-PE13-PadN11)") (class "Default")
      (node (ref "U3") (pin "N11") (pinfunction "PE13_N11") (pintype "bidirectional"))
    )
    (net (code "111") (name "unconnected-(U3A-PF0-PadE2)") (class "Default")
      (node (ref "U3") (pin "E2") (pinfunction "PF0_E2") (pintype "bidirectional"))
    )
    (net (code "112") (name "unconnected-(U3A-PF1-PadH3)") (class "Default")
      (node (ref "U3") (pin "H3") (pinfunction "PF1_H3") (pintype "bidirectional"))
    )
    (net (code "113") (name "unconnected-(U3A-PF2-PadH2)") (class "Default")
      (node (ref "U3") (pin "H2") (pinfunction "PF2_H2") (pintype "bidirectional"))
    )
    (net (code "114") (name "unconnected-(U3A-PF3-PadJ2)") (class "Default")
      (node (ref "U3") (pin "J2") (pinfunction "PF3_J2") (pintype "bidirectional"))
    )
    (net (code "115") (name "unconnected-(U3A-PF4-PadJ3)") (class "Default")
      (node (ref "U3") (pin "J3") (pinfunction "PF4_J3") (pintype "bidirectional"))
    )
    (net (code "116") (name "unconnected-(U3A-PF5-PadK3)") (class "Default")
      (node (ref "U3") (pin "K3") (pinfunction "PF5_K3") (pintype "bidirectional"))
    )
    (net (code "117") (name "unconnected-(U3A-PF6-PadK2)") (class "Default")
      (node (ref "U3") (pin "K2") (pinfunction "PF6_K2") (pintype "bidirectional"))
    )
    (net (code "118") (name "unconnected-(U3A-PF7-PadK1)") (class "Default")
      (node (ref "U3") (pin "K1") (pinfunction "PF7_K1") (pintype "bidirectional"))
    )
    (net (code "119") (name "unconnected-(U3A-PF8-PadL3)") (class "Default")
      (node (ref "U3") (pin "L3") (pinfunction "PF8_L3") (pintype "bidirectional"))
    )
    (net (code "120") (name "unconnected-(U3A-PF9-PadL2)") (class "Default")
      (node (ref "U3") (pin "L2") (pinfunction "PF9_L2") (pintype "bidirectional"))
    )
    (net (code "121") (name "unconnected-(U3A-PF10-PadL1)") (class "Default")
      (node (ref "U3") (pin "L1") (pinfunction "PF10_L1") (pintype "bidirectional"))
    )
    (net (code "122") (name "unconnected-(U3A-PF11-PadR6)") (class "Default")
      (node (ref "U3") (pin "R6") (pinfunction "PF11_R6") (pintype "bidirectional"))
    )
    (net (code "123") (name "unconnected-(U3A-PF14-PadR7)") (class "Default")
      (node (ref "U3") (pin "R7") (pinfunction "PF14_R7") (pintype "bidirectional"))
    )
    (net (code "124") (name "unconnected-(U3A-PF15-PadP7)") (class "Default")
      (node (ref "U3") (pin "P7") (pinfunction "PF15_P7") (pintype "bidirectional"))
    )
    (net (code "125") (name "unconnected-(U3B-PG0-PadN7)") (class "Default")
      (node (ref "U3") (pin "N7") (pinfunction "PG0_N7") (pintype "bidirectional"))
    )
    (net (code "126") (name "unconnected-(U3B-PG1-PadM7)") (class "Default")
      (node (ref "U3") (pin "M7") (pinfunction "PG1_M7") (pintype "bidirectional"))
    )
    (net (code "127") (name "unconnected-(U3B-PG5-PadK13)") (class "Default")
      (node (ref "U3") (pin "K13") (pinfunction "PG5_K13") (pintype "bidirectional"))
    )
    (net (code "128") (name "unconnected-(U3B-PG8-PadH14)") (class "Default")
      (node (ref "U3") (pin "H14") (pinfunction "PG8_H14") (pintype "bidirectional"))
    )
    (net (code "129") (name "unconnected-(U3B-PG9-PadC10)") (class "Default")
      (node (ref "U3") (pin "C10") (pinfunction "PG9_C10") (pintype "bidirectional"))
    )
    (net (code "130") (name "unconnected-(U3B-PG10-PadB10)") (class "Default")
      (node (ref "U3") (pin "B10") (pinfunction "PG10_B10") (pintype "bidirectional"))
    )
    (net (code "131") (name "unconnected-(U3B-PH2-PadF4)") (class "Default")
      (node (ref "U3") (pin "F4") (pinfunction "PH2_F4") (pintype "bidirectional"))
    )
    (net (code "132") (name "unconnected-(U3B-PH3-PadG4)") (class "Default")
      (node (ref "U3") (pin "G4") (pinfunction "PH3_G4") (pintype "bidirectional"))
    )
    (net (code "133") (name "unconnected-(U3B-PH4-PadH4)") (class "Default")
      (node (ref "U3") (pin "H4") (pinfunction "PH4_H4") (pintype "bidirectional"))
    )
    (net (code "134") (name "unconnected-(U3B-PH5-PadJ4)") (class "Default")
      (node (ref "U3") (pin "J4") (pinfunction "PH5_J4") (pintype "bidirectional"))
    )
    (net (code "135") (name "unconnected-(U3B-PH6-PadM11)") (class "Default")
      (node (ref "U3") (pin "M11") (pinfunction "PH6_M11") (pintype "bidirectional"))
    )
    (net (code "136") (name "unconnected-(U3B-PH9-PadM13)") (class "Default")
      (node (ref "U3") (pin "M13") (pinfunction "PH9_M13") (pintype "bidirectional"))
    )
    (net (code "137") (name "unconnected-(U3B-PH10-PadL13)") (class "Default")
      (node (ref "U3") (pin "L13") (pinfunction "PH10_L13") (pintype "bidirectional"))
    )
    (net (code "138") (name "unconnected-(U3B-PH11-PadL12)") (class "Default")
      (node (ref "U3") (pin "L12") (pinfunction "PH11_L12") (pintype "bidirectional"))
    )
    (net (code "139") (name "unconnected-(U3B-PH12-PadK12)") (class "Default")
      (node (ref "U3") (pin "K12") (pinfunction "PH12_K12") (pintype "bidirectional"))
    )
    (net (code "140") (name "unconnected-(U3B-PH13-PadE12)") (class "Default")
      (node (ref "U3") (pin "E12") (pinfunction "PH13_E12") (pintype "bidirectional"))
    )
    (net (code "141") (name "unconnected-(U3B-PH14-PadE13)") (class "Default")
      (node (ref "U3") (pin "E13") (pinfunction "PH14_E13") (pintype "bidirectional"))
    )
    (net (code "142") (name "unconnected-(U3B-PH15-PadD13)") (class "Default")
      (node (ref "U3") (pin "D13") (pinfunction "PH15_D13") (pintype "bidirectional"))
    )
    (net (code "143") (name "unconnected-(U3B-PI4-PadD4)") (class "Default")
      (node (ref "U3") (pin "D4") (pinfunction "PI4_D4") (pintype "bidirectional"))
    )
    (net (code "144") (name "unconnected-(U3B-PI8-PadD2)") (class "Default")
      (node (ref "U3") (pin "D2") (pinfunction "PI8_D2") (pintype "bidirectional"))
    )
    (net (code "145") (name "unconnected-(U3B-PI9-PadD3)") (class "Default")
      (node (ref "U3") (pin "D3") (pinfunction "PI9_D3") (pintype "bidirectional"))
    )
    (net (code "146") (name "unconnected-(U3B-PI10-PadE3)") (class "Default")
      (node (ref "U3") (pin "E3") (pinfunction "PI10_E3") (pintype "bidirectional"))
    )
    (net (code "147") (name "unconnected-(U3B-PI11-PadE4)") (class "Default")
      (node (ref "U3") (pin "E4") (pinfunction "PI11_E4") (pintype "bidirectional"))
    )
  )
)
